# probatio-rotary-8leds-5050.net
KiCad netlist of a schematic drawn in EAGLE
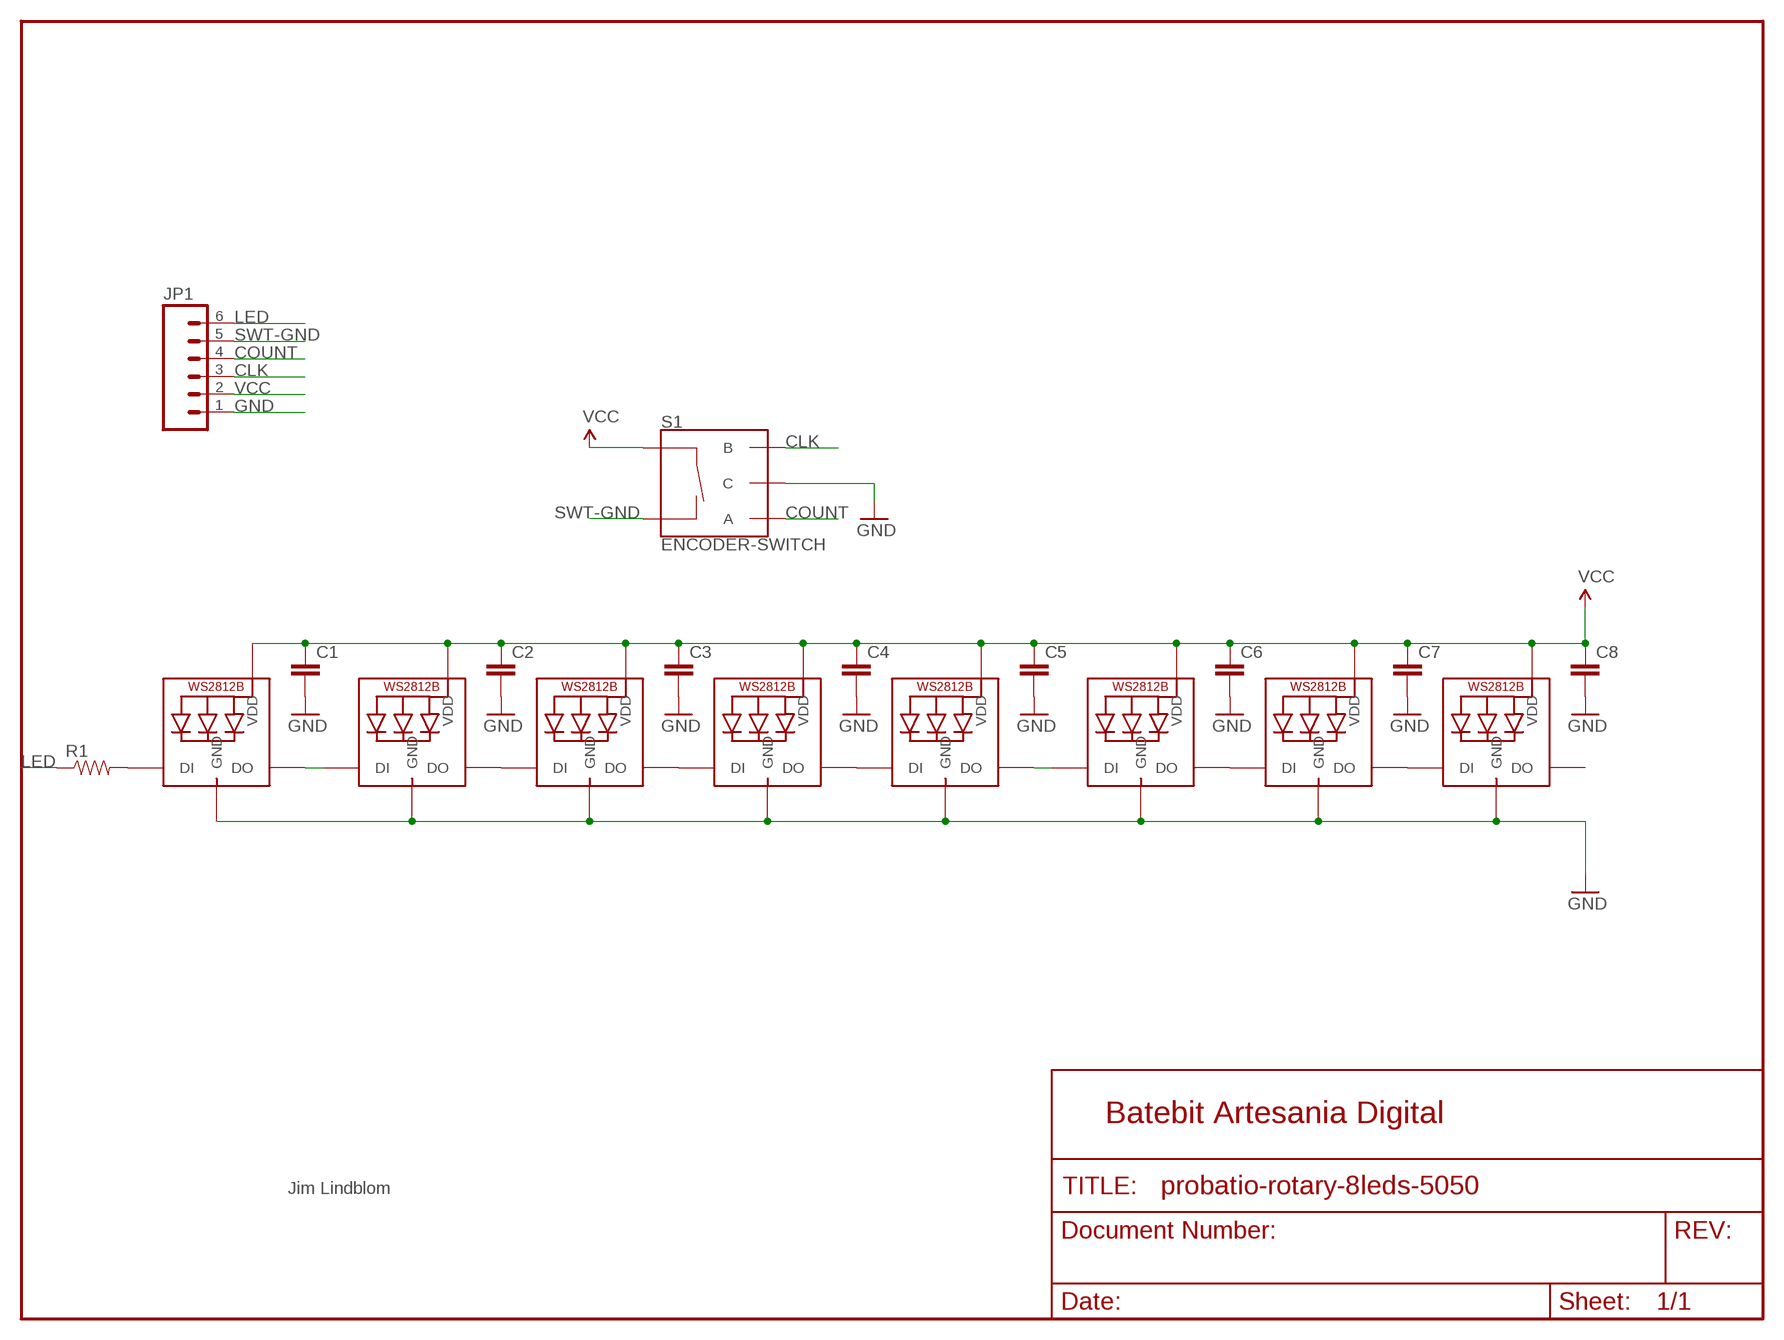
[diagram p0: schematic, sheet 1]

(export (version "E")
  (design (tool "Eeschema 10.0.6"))
  (components
    (comp (ref "C1")
      (value "CAP0805-CAP")
      (footprint "eagle-import:0805-CAP")
      (libsource (lib "eagle-import") (part "CAP0805-CAP"))
    )
    (comp (ref "C2")
      (value "CAP0805-CAP")
      (footprint "eagle-import:0805-CAP")
      (libsource (lib "eagle-import") (part "CAP0805-CAP"))
    )
    (comp (ref "C3")
      (value "CAP0805-CAP")
      (footprint "eagle-import:0805-CAP")
      (libsource (lib "eagle-import") (part "CAP0805-CAP"))
    )
    (comp (ref "C4")
      (value "CAP0805-CAP")
      (footprint "eagle-import:0805-CAP")
      (libsource (lib "eagle-import") (part "CAP0805-CAP"))
    )
    (comp (ref "C5")
      (value "CAP0805-CAP")
      (footprint "eagle-import:0805-CAP")
      (libsource (lib "eagle-import") (part "CAP0805-CAP"))
    )
    (comp (ref "C6")
      (value "CAP0805-CAP")
      (footprint "eagle-import:0805-CAP")
      (libsource (lib "eagle-import") (part "CAP0805-CAP"))
    )
    (comp (ref "C7")
      (value "CAP0805-CAP")
      (footprint "eagle-import:0805-CAP")
      (libsource (lib "eagle-import") (part "CAP0805-CAP"))
    )
    (comp (ref "C8")
      (value "CAP0805-CAP")
      (footprint "eagle-import:0805-CAP")
      (libsource (lib "eagle-import") (part "CAP0805-CAP"))
    )
    (comp (ref "JP1")
      (value "M06SILK_FEMALE_PTH")
      (footprint "eagle-import:1X06")
      (libsource (lib "eagle-import") (part "M06SILK_FEMALE_PTH"))
    )
    (comp (ref "LED1")
      (value "WS2812B5050")
      (footprint "eagle-import:WS2812B")
      (libsource (lib "eagle-import") (part "WS2812B5050"))
    )
    (comp (ref "LED2")
      (value "WS2812B5050")
      (footprint "eagle-import:WS2812B")
      (libsource (lib "eagle-import") (part "WS2812B5050"))
    )
    (comp (ref "LED3")
      (value "WS2812B5050")
      (footprint "eagle-import:WS2812B")
      (libsource (lib "eagle-import") (part "WS2812B5050"))
    )
    (comp (ref "LED4")
      (value "WS2812B5050")
      (footprint "eagle-import:WS2812B")
      (libsource (lib "eagle-import") (part "WS2812B5050"))
    )
    (comp (ref "LED5")
      (value "WS2812B5050")
      (footprint "eagle-import:WS2812B")
      (libsource (lib "eagle-import") (part "WS2812B5050"))
    )
    (comp (ref "LED6")
      (value "WS2812B5050")
      (footprint "eagle-import:WS2812B")
      (libsource (lib "eagle-import") (part "WS2812B5050"))
    )
    (comp (ref "LED7")
      (value "WS2812B5050")
      (footprint "eagle-import:WS2812B")
      (libsource (lib "eagle-import") (part "WS2812B5050"))
    )
    (comp (ref "LED8")
      (value "WS2812B5050")
      (footprint "eagle-import:WS2812B")
      (libsource (lib "eagle-import") (part "WS2812B5050"))
    )
    (comp (ref "R1")
      (value "RESISTOR0805-RES")
      (footprint "eagle-import:0805-RES")
      (libsource (lib "eagle-import") (part "RESISTOR0805-RES"))
    )
    (comp (ref "S1")
      (value "ENCODER-SWITCH")
      (footprint "eagle-import:ROTARY_ENC_PLAIN")
      (libsource (lib "eagle-import") (part "ENCODER-SWITCH"))
    )
  )
  (nets
    (net (code "1") (name "/CLK") (class "Default")
      (node (ref "JP1") (pin "3") (pinfunction "3_3") (pintype "passive"))
      (node (ref "S1") (pin "B") (pinfunction "B_B") (pintype "bidirectional"))
    )
    (net (code "2") (name "/COUNT") (class "Default")
      (node (ref "JP1") (pin "4") (pinfunction "4_4") (pintype "passive"))
      (node (ref "S1") (pin "A") (pinfunction "A_A") (pintype "bidirectional"))
    )
    (net (code "3") (name "/LED") (class "Default")
      (node (ref "JP1") (pin "6") (pinfunction "6_6") (pintype "passive"))
      (node (ref "R1") (pin "1") (pinfunction "1_1") (pintype "passive"))
    )
    (net (code "4") (name "/SWT-GND") (class "Default")
      (node (ref "JP1") (pin "5") (pinfunction "5_5") (pintype "passive"))
      (node (ref "S1") (pin "SW-") (pinfunction "SW-_SW-") (pintype "bidirectional"))
    )
    (net (code "5") (name "GND") (class "Default")
      (node (ref "C1") (pin "2") (pinfunction "2_2") (pintype "passive"))
      (node (ref "C2") (pin "2") (pinfunction "2_2") (pintype "passive"))
      (node (ref "C3") (pin "2") (pinfunction "2_2") (pintype "passive"))
      (node (ref "C4") (pin "2") (pinfunction "2_2") (pintype "passive"))
      (node (ref "C5") (pin "2") (pinfunction "2_2") (pintype "passive"))
      (node (ref "C6") (pin "2") (pinfunction "2_2") (pintype "passive"))
      (node (ref "C7") (pin "2") (pinfunction "2_2") (pintype "passive"))
      (node (ref "C8") (pin "2") (pinfunction "2_2") (pintype "passive"))
      (node (ref "JP1") (pin "1") (pinfunction "1_1") (pintype "passive"))
      (node (ref "LED1") (pin "3-GND") (pinfunction "GND_3-GND") (pintype "power_in"))
      (node (ref "LED2") (pin "3-GND") (pinfunction "GND_3-GND") (pintype "power_in"))
      (node (ref "LED3") (pin "3-GND") (pinfunction "GND_3-GND") (pintype "power_in"))
      (node (ref "LED4") (pin "3-GND") (pinfunction "GND_3-GND") (pintype "power_in"))
      (node (ref "LED5") (pin "3-GND") (pinfunction "GND_3-GND") (pintype "power_in"))
      (node (ref "LED6") (pin "3-GND") (pinfunction "GND_3-GND") (pintype "power_in"))
      (node (ref "LED7") (pin "3-GND") (pinfunction "GND_3-GND") (pintype "power_in"))
      (node (ref "LED8") (pin "3-GND") (pinfunction "GND_3-GND") (pintype "power_in"))
      (node (ref "S1") (pin "C") (pinfunction "C_C") (pintype "bidirectional"))
    )
    (net (code "6") (name "Net-(LED1-DI)") (class "Default")
      (node (ref "LED1") (pin "4-DIN") (pinfunction "DI_4-DIN") (pintype "input"))
      (node (ref "R1") (pin "2") (pinfunction "2_2") (pintype "passive"))
    )
    (net (code "7") (name "Net-(LED1-DO)") (class "Default")
      (node (ref "LED1") (pin "2-DOUT") (pinfunction "DO_2-DOUT") (pintype "output"))
      (node (ref "LED2") (pin "4-DIN") (pinfunction "DI_4-DIN") (pintype "input"))
    )
    (net (code "8") (name "Net-(LED2-DO)") (class "Default")
      (node (ref "LED2") (pin "2-DOUT") (pinfunction "DO_2-DOUT") (pintype "output"))
      (node (ref "LED3") (pin "4-DIN") (pinfunction "DI_4-DIN") (pintype "input"))
    )
    (net (code "9") (name "Net-(LED3-DO)") (class "Default")
      (node (ref "LED3") (pin "2-DOUT") (pinfunction "DO_2-DOUT") (pintype "output"))
      (node (ref "LED4") (pin "4-DIN") (pinfunction "DI_4-DIN") (pintype "input"))
    )
    (net (code "10") (name "Net-(LED4-DO)") (class "Default")
      (node (ref "LED4") (pin "2-DOUT") (pinfunction "DO_2-DOUT") (pintype "output"))
      (node (ref "LED5") (pin "4-DIN") (pinfunction "DI_4-DIN") (pintype "input"))
    )
    (net (code "11") (name "Net-(LED5-DO)") (class "Default")
      (node (ref "LED5") (pin "2-DOUT") (pinfunction "DO_2-DOUT") (pintype "output"))
      (node (ref "LED6") (pin "4-DIN") (pinfunction "DI_4-DIN") (pintype "input"))
    )
    (net (code "12") (name "Net-(LED6-DO)") (class "Default")
      (node (ref "LED6") (pin "2-DOUT") (pinfunction "DO_2-DOUT") (pintype "output"))
      (node (ref "LED7") (pin "4-DIN") (pinfunction "DI_4-DIN") (pintype "input"))
    )
    (net (code "13") (name "Net-(LED7-DO)") (class "Default")
      (node (ref "LED7") (pin "2-DOUT") (pinfunction "DO_2-DOUT") (pintype "output"))
      (node (ref "LED8") (pin "4-DIN") (pinfunction "DI_4-DIN") (pintype "input"))
    )
    (net (code "14") (name "VCC") (class "Default")
      (node (ref "C1") (pin "1") (pinfunction "1_1") (pintype "passive"))
      (node (ref "C2") (pin "1") (pinfunction "1_1") (pintype "passive"))
      (node (ref "C3") (pin "1") (pinfunction "1_1") (pintype "passive"))
      (node (ref "C4") (pin "1") (pinfunction "1_1") (pintype "passive"))
      (node (ref "C5") (pin "1") (pinfunction "1_1") (pintype "passive"))
      (node (ref "C6") (pin "1") (pinfunction "1_1") (pintype "passive"))
      (node (ref "C7") (pin "1") (pinfunction "1_1") (pintype "passive"))
      (node (ref "C8") (pin "1") (pinfunction "1_1") (pintype "passive"))
      (node (ref "JP1") (pin "2") (pinfunction "2_2") (pintype "passive"))
      (node (ref "LED1") (pin "1-VDD") (pinfunction "VDD_1-VDD") (pintype "power_in"))
      (node (ref "LED2") (pin "1-VDD") (pinfunction "VDD_1-VDD") (pintype "power_in"))
      (node (ref "LED3") (pin "1-VDD") (pinfunction "VDD_1-VDD") (pintype "power_in"))
      (node (ref "LED4") (pin "1-VDD") (pinfunction "VDD_1-VDD") (pintype "power_in"))
      (node (ref "LED5") (pin "1-VDD") (pinfunction "VDD_1-VDD") (pintype "power_in"))
      (node (ref "LED6") (pin "1-VDD") (pinfunction "VDD_1-VDD") (pintype "power_in"))
      (node (ref "LED7") (pin "1-VDD") (pinfunction "VDD_1-VDD") (pintype "power_in"))
      (node (ref "LED8") (pin "1-VDD") (pinfunction "VDD_1-VDD") (pintype "power_in"))
      (node (ref "S1") (pin "SW+") (pinfunction "SW+_SW+") (pintype "bidirectional"))
    )
    (net (code "15") (name "unconnected-(LED8-DO-Pad2-DOUT)") (class "Default")
      (node (ref "LED8") (pin "2-DOUT") (pinfunction "DO_2-DOUT") (pintype "output"))
    )
  )
)
